# 51.net
KiCad netlist of a schematic drawn in EasyEDA Pro
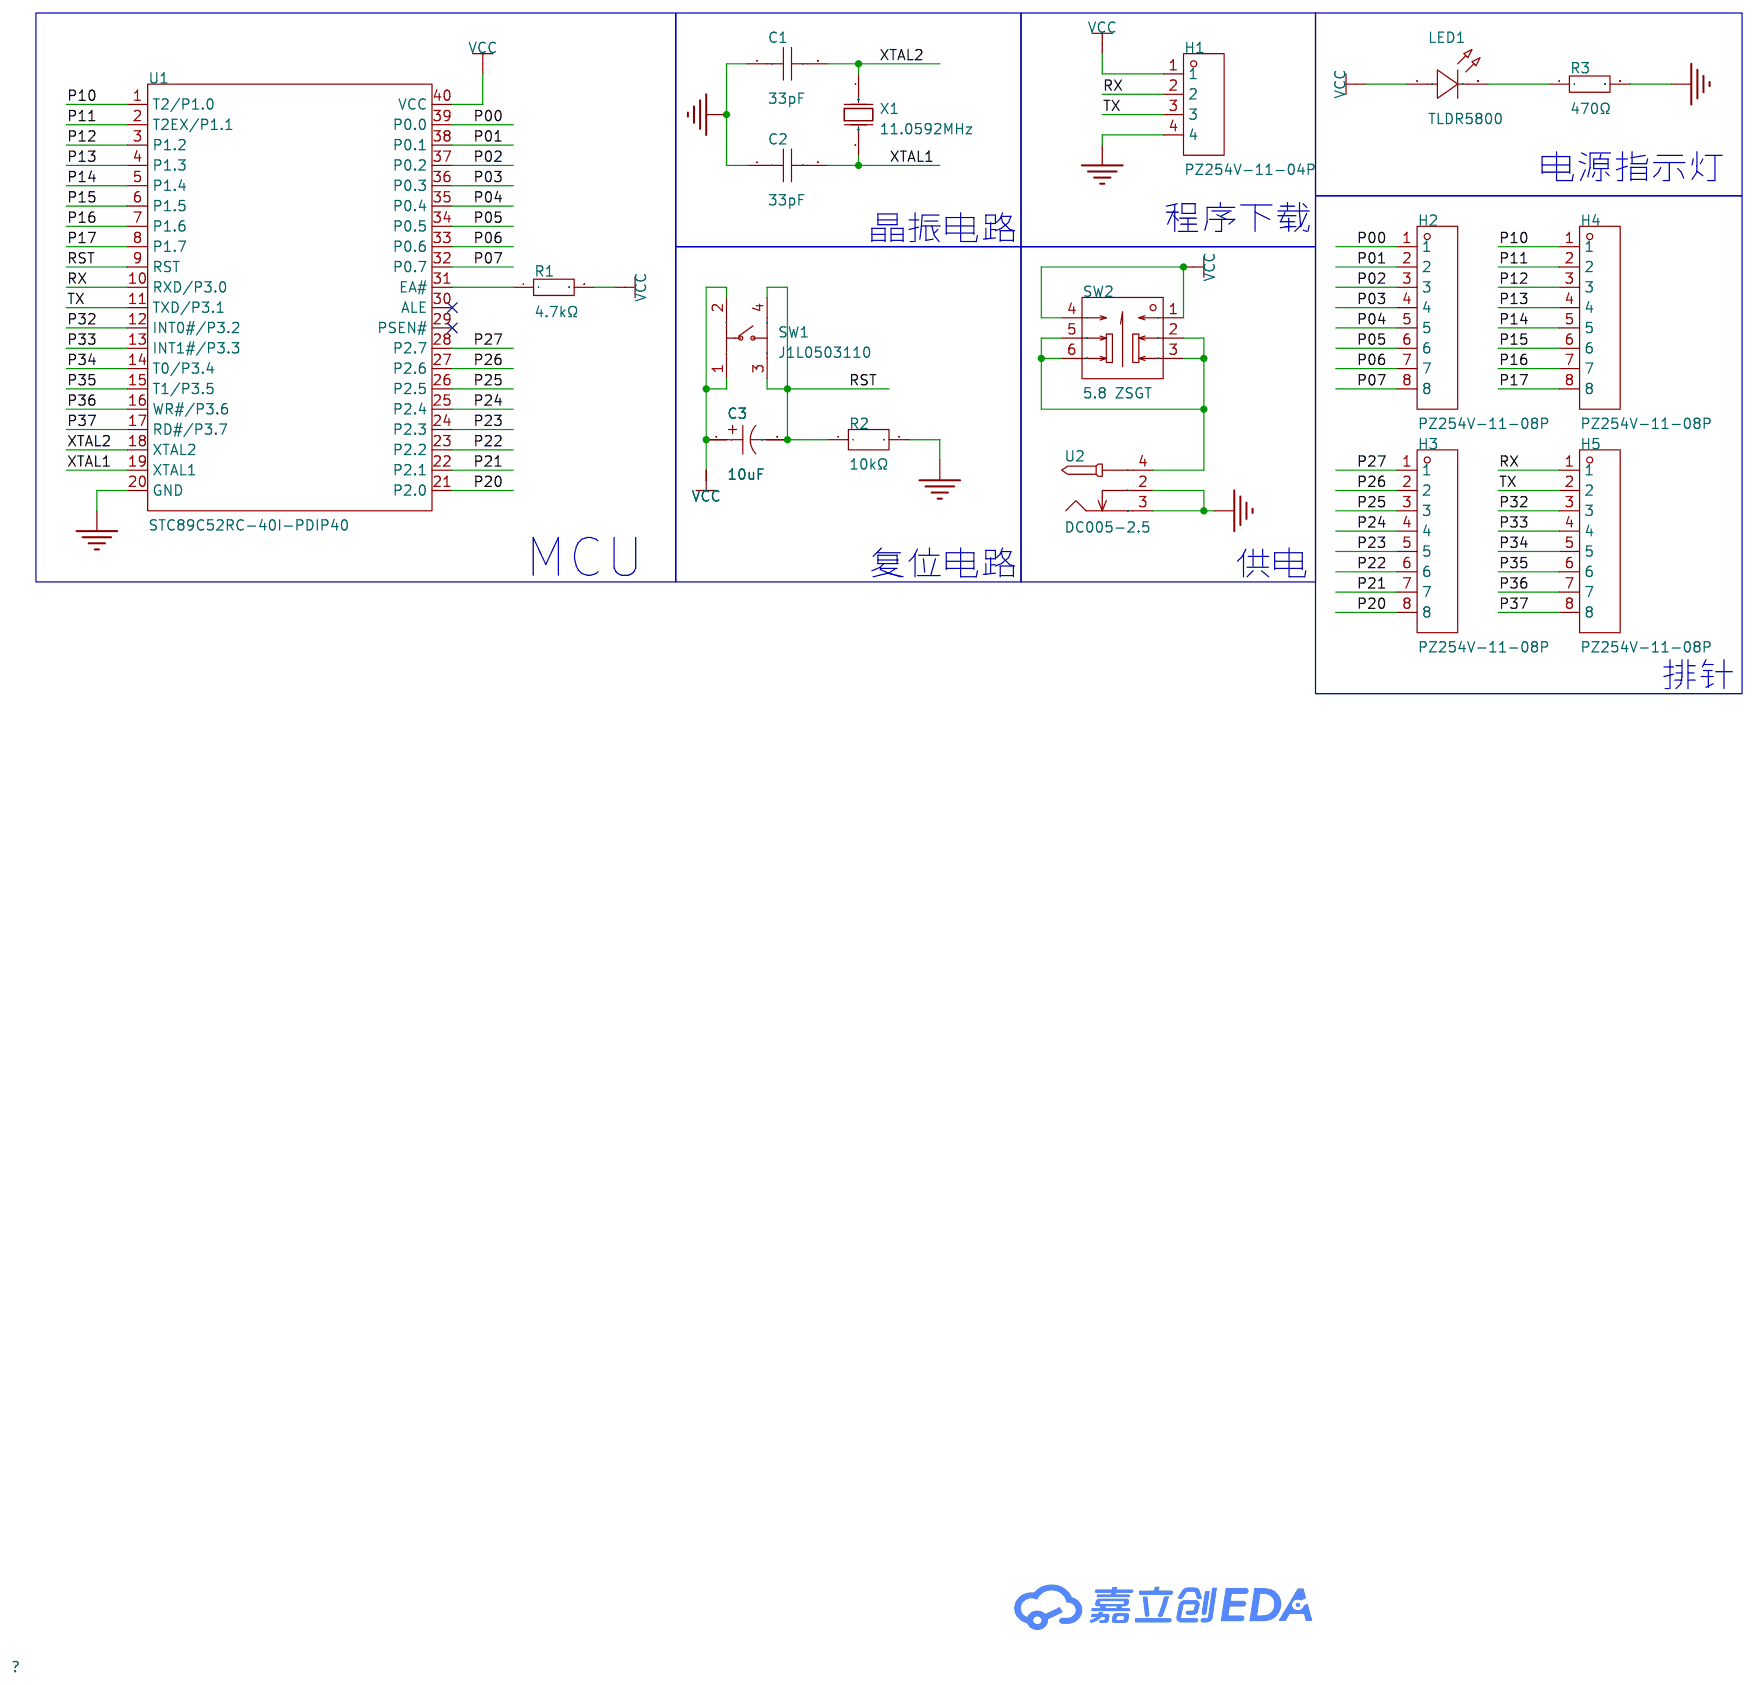
[diagram p0: schematic sheet]

(export (version "E")
  (design (tool "Eeschema 10.0.6"))
  (components
    (comp (ref "C1")
      (value "33pF")
      (footprint "easyedapro:CAP-TH_L8.5-W5.0-P5.00-D1.2")
      (description "容值:33pF;精度:±5%;额定电压:50V;温度系数:C0G;")
      (fields (field (name "Manufacturer Part") "CC4-0805N330J500F3") (field (name "Manufacturer") "FH(风华)"))
      (libsource (lib "easyedapro") (part "CC4-0805N330J500F3"))
    )
    (comp (ref "C2")
      (value "33pF")
      (footprint "easyedapro:CAP-TH_L8.5-W5.0-P5.00-D1.2")
      (description "容值:33pF;精度:±5%;额定电压:50V;温度系数:C0G;")
      (fields (field (name "Manufacturer Part") "CC4-0805N330J500F3") (field (name "Manufacturer") "FH(风华)"))
      (libsource (lib "easyedapro") (part "CC4-0805N330J500F3"))
    )
    (comp (ref "C3")
      (value "10uF")
      (footprint "easyedapro:CAP-TH_BD5.0-P2.00-D0.5-FD-A")
      (description "容值:10uF;精度:±20%;额定电压:50V;纹波电流:180mA@100kHz;等效串联电阻(ESR):1.3Ω@100kHz;")
      (fields (field (name "Manufacturer Part") "ERG50V10M5X11") (field (name "Manufacturer") "JIERR(捷而瑞)"))
      (libsource (lib "easyedapro") (part "ERG50V10M5X11"))
    )
    (comp (ref "H1")
      (value "PZ254V-11-04P")
      (footprint "easyedapro:HDR-TH_4P-P2.54-V-M")
      (fields (field (name "Manufacturer") "XFCN(兴飞)"))
      (libsource (lib "easyedapro") (part "PZ254V-11-04P_C2691448"))
    )
    (comp (ref "H2")
      (value "PZ254V-11-08P")
      (footprint "easyedapro:HDR-TH_8P-P2.54-V-M")
      (fields (field (name "Manufacturer") "XFCN(兴飞)"))
      (libsource (lib "easyedapro") (part "PZ254V-11-08P"))
    )
    (comp (ref "H3")
      (value "PZ254V-11-08P")
      (footprint "easyedapro:HDR-TH_8P-P2.54-V-M")
      (fields (field (name "Manufacturer") "XFCN(兴飞)"))
      (libsource (lib "easyedapro") (part "PZ254V-11-08P"))
    )
    (comp (ref "H4")
      (value "PZ254V-11-08P")
      (footprint "easyedapro:HDR-TH_8P-P2.54-V-M")
      (fields (field (name "Manufacturer") "XFCN(兴飞)"))
      (libsource (lib "easyedapro") (part "PZ254V-11-08P"))
    )
    (comp (ref "H5")
      (value "PZ254V-11-08P")
      (footprint "easyedapro:HDR-TH_8P-P2.54-V-M")
      (fields (field (name "Manufacturer") "XFCN(兴飞)"))
      (libsource (lib "easyedapro") (part "PZ254V-11-08P"))
    )
    (comp (ref "LED1")
      (value "TLDR5800")
      (footprint "easyedapro:LED-TH_BD5.0-P2.54-FD-1")
      (fields (field (name "Manufacturer") "VISHAY(威世)"))
      (libsource (lib "easyedapro") (part "TLDR5800"))
    )
    (comp (ref "R1")
      (value "4.7kΩ")
      (footprint "easyedapro:RES-TH_BD2.4-L6.3-P10.30-D0.6")
      (description "电阻类型:金属膜电阻;阻值:4.7kΩ;精度:±1%;功率:250mW;温度系数:±50ppm/°C;")
      (fields (field (name "Manufacturer Part") "MFR-25FTE52-4K7") (field (name "Manufacturer") "YAGEO(国巨)"))
      (libsource (lib "easyedapro") (part "MFR-25FTE52-4K7"))
    )
    (comp (ref "R2")
      (value "10kΩ")
      (footprint "easyedapro:RES-TH_BD2.7-L6.2-P10.20-D0.4")
      (description "电阻类型:金属膜电阻;阻值:10kΩ;精度:±1%;功率:250mW;温度系数:±100ppm/°C;")
      (fields (field (name "Manufacturer Part") "MF1/4W-10K±1%-ST52") (field (name "Manufacturer") "VO(翔胜)"))
      (libsource (lib "easyedapro") (part "MF1/4W-10K±1%-ST52"))
    )
    (comp (ref "R3")
      (value "470Ω")
      (footprint "easyedapro:RES-TH_BD2.3-L6.5-P10.50-D0.5")
      (description "电阻类型:金属膜电阻;阻值:470Ω;精度:±1%;功率:500mW;温度系数:±100ppm/°C;")
      (fields
        (field (name "Manufacturer Part") "MF1/2WS-470Ω±1% T")
        (field (name "Manufacturer") "CCO(千志电子)")
      )
      (libsource (lib "easyedapro") (part "MF1/2WS-470Ω±1% T52"))
    )
    (comp (ref "SW1")
      (value "J1L0503110")
      (footprint "easyedapro:SW-TH_4P-L6.0-W6.0-P4.50-LS6.3")
      (fields (field (name "Manufacturer") "SAMZO(三佐)"))
      (libsource (lib "easyedapro") (part "J1L0503110"))
    )
    (comp (ref "SW2")
      (value "5.8 ZSGT")
      (footprint "easyedapro:SW-TH_5.8ZSGT")
      (description "电路结构:双刀双掷;自锁/无锁:自锁;安装方式:直插;触点电流:110mA;额定电压:30V;带灯:不带;作用力:1.5N;工作寿命:10万次;")
      (fields (field (name "Manufacturer") "SHOU HAN(首韩)"))
      (libsource (lib "easyedapro") (part "5.8 ZSGT"))
    )
    (comp (ref "U1")
      (value "STC89C52RC-40I-PDIP40")
      (footprint "easyedapro:DIP-40_L52.0-W13.7-P2.54-LS15.2-BL")
      (description "CPU内核:51系列;应用领域:-;")
      (fields (field (name "Manufacturer") "STC"))
      (libsource (lib "easyedapro") (part "STC89C52RC-40I"))
    )
    (comp (ref "U2")
      (value "DC005-2.5")
      (footprint "easyedapro:DC-IN-TH_DC005-2.5MM")
      (description "连接器类型:DC电源插座;安装方式:弯插;触点内径:2.5mm;触点外径:6.3mm;额定电流:500mA;额定电压:12V;工作温度:-30°C~+70°C;")
      (fields (field (name "Manufacturer") "SHOU HAN(首韩)"))
      (libsource (lib "easyedapro") (part "DC005-2.5"))
    )
    (comp (ref "X1")
      (value "11.0592MHz")
      (footprint "easyedapro:HC-49US_L11.5-W4.5-P4.88")
      (description "晶振类型:直插晶振;频率:11.0592MHz;常温频差:±20ppm;负载电容:20pF;频率稳定度:±30ppm;")
      (fields
        (field (name "Manufacturer Part") "X49SD110592MSD2SC")
        (field (name "Manufacturer") "YXC(扬兴晶振)")
      )
      (libsource (lib "easyedapro") (part "X49SD110592MSD2SC"))
    )
  )
  (nets
    (net (code "1") (name "/P00") (class "Default")
      (node (ref "H2") (pin "1") (pinfunction "1_1") (pintype "unspecified"))
      (node (ref "U1") (pin "39") (pinfunction "P0.0_39") (pintype "unspecified"))
    )
    (net (code "2") (name "/P01") (class "Default")
      (node (ref "H2") (pin "2") (pinfunction "2_2") (pintype "unspecified"))
      (node (ref "U1") (pin "38") (pinfunction "P0.1_38") (pintype "unspecified"))
    )
    (net (code "3") (name "/P02") (class "Default")
      (node (ref "H2") (pin "3") (pinfunction "3_3") (pintype "unspecified"))
      (node (ref "U1") (pin "37") (pinfunction "P0.2_37") (pintype "unspecified"))
    )
    (net (code "4") (name "/P03") (class "Default")
      (node (ref "H2") (pin "4") (pinfunction "4_4") (pintype "unspecified"))
      (node (ref "U1") (pin "36") (pinfunction "P0.3_36") (pintype "unspecified"))
    )
    (net (code "5") (name "/P04") (class "Default")
      (node (ref "H2") (pin "5") (pinfunction "5_5") (pintype "unspecified"))
      (node (ref "U1") (pin "35") (pinfunction "P0.4_35") (pintype "unspecified"))
    )
    (net (code "6") (name "/P05") (class "Default")
      (node (ref "H2") (pin "6") (pinfunction "6_6") (pintype "unspecified"))
      (node (ref "U1") (pin "34") (pinfunction "P0.5_34") (pintype "unspecified"))
    )
    (net (code "7") (name "/P06") (class "Default")
      (node (ref "H2") (pin "7") (pinfunction "7_7") (pintype "unspecified"))
      (node (ref "U1") (pin "33") (pinfunction "P0.6_33") (pintype "unspecified"))
    )
    (net (code "8") (name "/P07") (class "Default")
      (node (ref "H2") (pin "8") (pinfunction "8_8") (pintype "unspecified"))
      (node (ref "U1") (pin "32") (pinfunction "P0.7_32") (pintype "unspecified"))
    )
    (net (code "9") (name "/P10") (class "Default")
      (node (ref "H4") (pin "1") (pinfunction "1_1") (pintype "unspecified"))
      (node (ref "U1") (pin "1") (pinfunction "T2/P1.0_1") (pintype "unspecified"))
    )
    (net (code "10") (name "/P11") (class "Default")
      (node (ref "H4") (pin "2") (pinfunction "2_2") (pintype "unspecified"))
      (node (ref "U1") (pin "2") (pinfunction "T2EX/P1.1_2") (pintype "unspecified"))
    )
    (net (code "11") (name "/P12") (class "Default")
      (node (ref "H4") (pin "3") (pinfunction "3_3") (pintype "unspecified"))
      (node (ref "U1") (pin "3") (pinfunction "P1.2_3") (pintype "unspecified"))
    )
    (net (code "12") (name "/P13") (class "Default")
      (node (ref "H4") (pin "4") (pinfunction "4_4") (pintype "unspecified"))
      (node (ref "U1") (pin "4") (pinfunction "P1.3_4") (pintype "unspecified"))
    )
    (net (code "13") (name "/P14") (class "Default")
      (node (ref "H4") (pin "5") (pinfunction "5_5") (pintype "unspecified"))
      (node (ref "U1") (pin "5") (pinfunction "P1.4_5") (pintype "unspecified"))
    )
    (net (code "14") (name "/P15") (class "Default")
      (node (ref "H4") (pin "6") (pinfunction "6_6") (pintype "unspecified"))
      (node (ref "U1") (pin "6") (pinfunction "P1.5_6") (pintype "unspecified"))
    )
    (net (code "15") (name "/P16") (class "Default")
      (node (ref "H4") (pin "7") (pinfunction "7_7") (pintype "unspecified"))
      (node (ref "U1") (pin "7") (pinfunction "P1.6_7") (pintype "unspecified"))
    )
    (net (code "16") (name "/P17") (class "Default")
      (node (ref "H4") (pin "8") (pinfunction "8_8") (pintype "unspecified"))
      (node (ref "U1") (pin "8") (pinfunction "P1.7_8") (pintype "unspecified"))
    )
    (net (code "17") (name "/P20") (class "Default")
      (node (ref "H3") (pin "8") (pinfunction "8_8") (pintype "unspecified"))
      (node (ref "U1") (pin "21") (pinfunction "P2.0_21") (pintype "unspecified"))
    )
    (net (code "18") (name "/P21") (class "Default")
      (node (ref "H3") (pin "7") (pinfunction "7_7") (pintype "unspecified"))
      (node (ref "U1") (pin "22") (pinfunction "P2.1_22") (pintype "unspecified"))
    )
    (net (code "19") (name "/P22") (class "Default")
      (node (ref "H3") (pin "6") (pinfunction "6_6") (pintype "unspecified"))
      (node (ref "U1") (pin "23") (pinfunction "P2.2_23") (pintype "unspecified"))
    )
    (net (code "20") (name "/P23") (class "Default")
      (node (ref "H3") (pin "5") (pinfunction "5_5") (pintype "unspecified"))
      (node (ref "U1") (pin "24") (pinfunction "P2.3_24") (pintype "unspecified"))
    )
    (net (code "21") (name "/P24") (class "Default")
      (node (ref "H3") (pin "4") (pinfunction "4_4") (pintype "unspecified"))
      (node (ref "U1") (pin "25") (pinfunction "P2.4_25") (pintype "unspecified"))
    )
    (net (code "22") (name "/P25") (class "Default")
      (node (ref "H3") (pin "3") (pinfunction "3_3") (pintype "unspecified"))
      (node (ref "U1") (pin "26") (pinfunction "P2.5_26") (pintype "unspecified"))
    )
    (net (code "23") (name "/P26") (class "Default")
      (node (ref "H3") (pin "2") (pinfunction "2_2") (pintype "unspecified"))
      (node (ref "U1") (pin "27") (pinfunction "P2.6_27") (pintype "unspecified"))
    )
    (net (code "24") (name "/P27") (class "Default")
      (node (ref "H3") (pin "1") (pinfunction "1_1") (pintype "unspecified"))
      (node (ref "U1") (pin "28") (pinfunction "P2.7_28") (pintype "unspecified"))
    )
    (net (code "25") (name "/P32") (class "Default")
      (node (ref "H5") (pin "3") (pinfunction "3_3") (pintype "unspecified"))
      (node (ref "U1") (pin "12") (pinfunction "INT0#/P3.2_12") (pintype "unspecified"))
    )
    (net (code "26") (name "/P33") (class "Default")
      (node (ref "H5") (pin "4") (pinfunction "4_4") (pintype "unspecified"))
      (node (ref "U1") (pin "13") (pinfunction "INT1#/P3.3_13") (pintype "unspecified"))
    )
    (net (code "27") (name "/P34") (class "Default")
      (node (ref "H5") (pin "5") (pinfunction "5_5") (pintype "unspecified"))
      (node (ref "U1") (pin "14") (pinfunction "T0/P3.4_14") (pintype "unspecified"))
    )
    (net (code "28") (name "/P35") (class "Default")
      (node (ref "H5") (pin "6") (pinfunction "6_6") (pintype "unspecified"))
      (node (ref "U1") (pin "15") (pinfunction "T1/P3.5_15") (pintype "unspecified"))
    )
    (net (code "29") (name "/P36") (class "Default")
      (node (ref "H5") (pin "7") (pinfunction "7_7") (pintype "unspecified"))
      (node (ref "U1") (pin "16") (pinfunction "WR#/P3.6_16") (pintype "unspecified"))
    )
    (net (code "30") (name "/P37") (class "Default")
      (node (ref "H5") (pin "8") (pinfunction "8_8") (pintype "unspecified"))
      (node (ref "U1") (pin "17") (pinfunction "RD#/P3.7_17") (pintype "unspecified"))
    )
    (net (code "31") (name "/RST") (class "Default")
      (node (ref "C3") (pin "2") (pinfunction "2_2") (pintype "input"))
      (node (ref "R2") (pin "1") (pinfunction "1_1") (pintype "unspecified"))
      (node (ref "SW1") (pin "3") (pinfunction "3_3") (pintype "unspecified"))
      (node (ref "SW1") (pin "4") (pinfunction "4_4") (pintype "unspecified"))
      (node (ref "U1") (pin "9") (pinfunction "RST_9") (pintype "unspecified"))
    )
    (net (code "32") (name "/RX") (class "Default")
      (node (ref "H1") (pin "2") (pinfunction "2_2") (pintype "unspecified"))
      (node (ref "H5") (pin "1") (pinfunction "1_1") (pintype "unspecified"))
      (node (ref "U1") (pin "10") (pinfunction "RXD/P3.0_10") (pintype "unspecified"))
    )
    (net (code "33") (name "/TX") (class "Default")
      (node (ref "H1") (pin "3") (pinfunction "3_3") (pintype "unspecified"))
      (node (ref "H5") (pin "2") (pinfunction "2_2") (pintype "unspecified"))
      (node (ref "U1") (pin "11") (pinfunction "TXD/P3.1_11") (pintype "unspecified"))
    )
    (net (code "34") (name "/XTAL1") (class "Default")
      (node (ref "C2") (pin "2") (pinfunction "2_2") (pintype "unspecified"))
      (node (ref "U1") (pin "19") (pinfunction "XTAL1_19") (pintype "unspecified"))
      (node (ref "X1") (pin "2") (pinfunction "OSC2_2") (pintype "input"))
    )
    (net (code "35") (name "/XTAL2") (class "Default")
      (node (ref "C1") (pin "2") (pinfunction "2_2") (pintype "unspecified"))
      (node (ref "U1") (pin "18") (pinfunction "XTAL2_18") (pintype "unspecified"))
      (node (ref "X1") (pin "1") (pinfunction "OSC1_1") (pintype "input"))
    )
    (net (code "36") (name "GND") (class "Default")
      (node (ref "C1") (pin "1") (pinfunction "1_1") (pintype "unspecified"))
      (node (ref "C2") (pin "1") (pinfunction "1_1") (pintype "unspecified"))
      (node (ref "H1") (pin "4") (pinfunction "4_4") (pintype "unspecified"))
      (node (ref "R2") (pin "2") (pinfunction "2_2") (pintype "unspecified"))
      (node (ref "R3") (pin "2") (pinfunction "2_2") (pintype "unspecified"))
      (node (ref "U1") (pin "20") (pinfunction "GND_20") (pintype "unspecified"))
      (node (ref "U2") (pin "2") (pinfunction "2_2") (pintype "unspecified"))
      (node (ref "U2") (pin "3") (pinfunction "3_3") (pintype "unspecified"))
    )
    (net (code "37") (name "Net-(LED1-K)") (class "Default")
      (node (ref "LED1") (pin "2") (pinfunction "K_2") (pintype "unspecified"))
      (node (ref "R3") (pin "1") (pinfunction "1_1") (pintype "unspecified"))
    )
    (net (code "38") (name "Net-(SW2-Pad2)") (class "Default")
      (node (ref "SW2") (pin "2") (pinfunction "2_2") (pintype "unspecified"))
      (node (ref "SW2") (pin "3") (pinfunction "3_3") (pintype "unspecified"))
      (node (ref "SW2") (pin "5") (pinfunction "5_5") (pintype "unspecified"))
      (node (ref "SW2") (pin "6") (pinfunction "6_6") (pintype "unspecified"))
      (node (ref "U2") (pin "4") (pinfunction "4_4") (pintype "unspecified"))
    )
    (net (code "39") (name "Net-(U1-EA#)") (class "Default")
      (node (ref "R1") (pin "1") (pinfunction "1_1") (pintype "unspecified"))
      (node (ref "U1") (pin "31") (pinfunction "EA#_31") (pintype "unspecified"))
    )
    (net (code "40") (name "VCC") (class "Default")
      (node (ref "C3") (pin "1") (pinfunction "1_1") (pintype "input"))
      (node (ref "H1") (pin "1") (pinfunction "1_1") (pintype "unspecified"))
      (node (ref "LED1") (pin "1") (pinfunction "A_1") (pintype "unspecified"))
      (node (ref "R1") (pin "2") (pinfunction "2_2") (pintype "unspecified"))
      (node (ref "SW1") (pin "1") (pinfunction "1_1") (pintype "unspecified"))
      (node (ref "SW1") (pin "2") (pinfunction "2_2") (pintype "unspecified"))
      (node (ref "SW2") (pin "1") (pinfunction "1_1") (pintype "unspecified"))
      (node (ref "SW2") (pin "4") (pinfunction "4_4") (pintype "unspecified"))
      (node (ref "U1") (pin "40") (pinfunction "VCC_40") (pintype "unspecified"))
    )
    (net (code "41") (name "unconnected-(U1-ALE-Pad30)") (class "Default")
      (node (ref "U1") (pin "30") (pinfunction "ALE_30") (pintype "unspecified+no_connect"))
    )
    (net (code "42") (name "unconnected-(U1-PSEN#-Pad29)") (class "Default")
      (node (ref "U1") (pin "29") (pinfunction "PSEN#_29") (pintype "unspecified+no_connect"))
    )
  )
)
